# Adafruit_USB_Type_C_Downstream_Breakout_.net
KiCad netlist of a schematic drawn in EAGLE
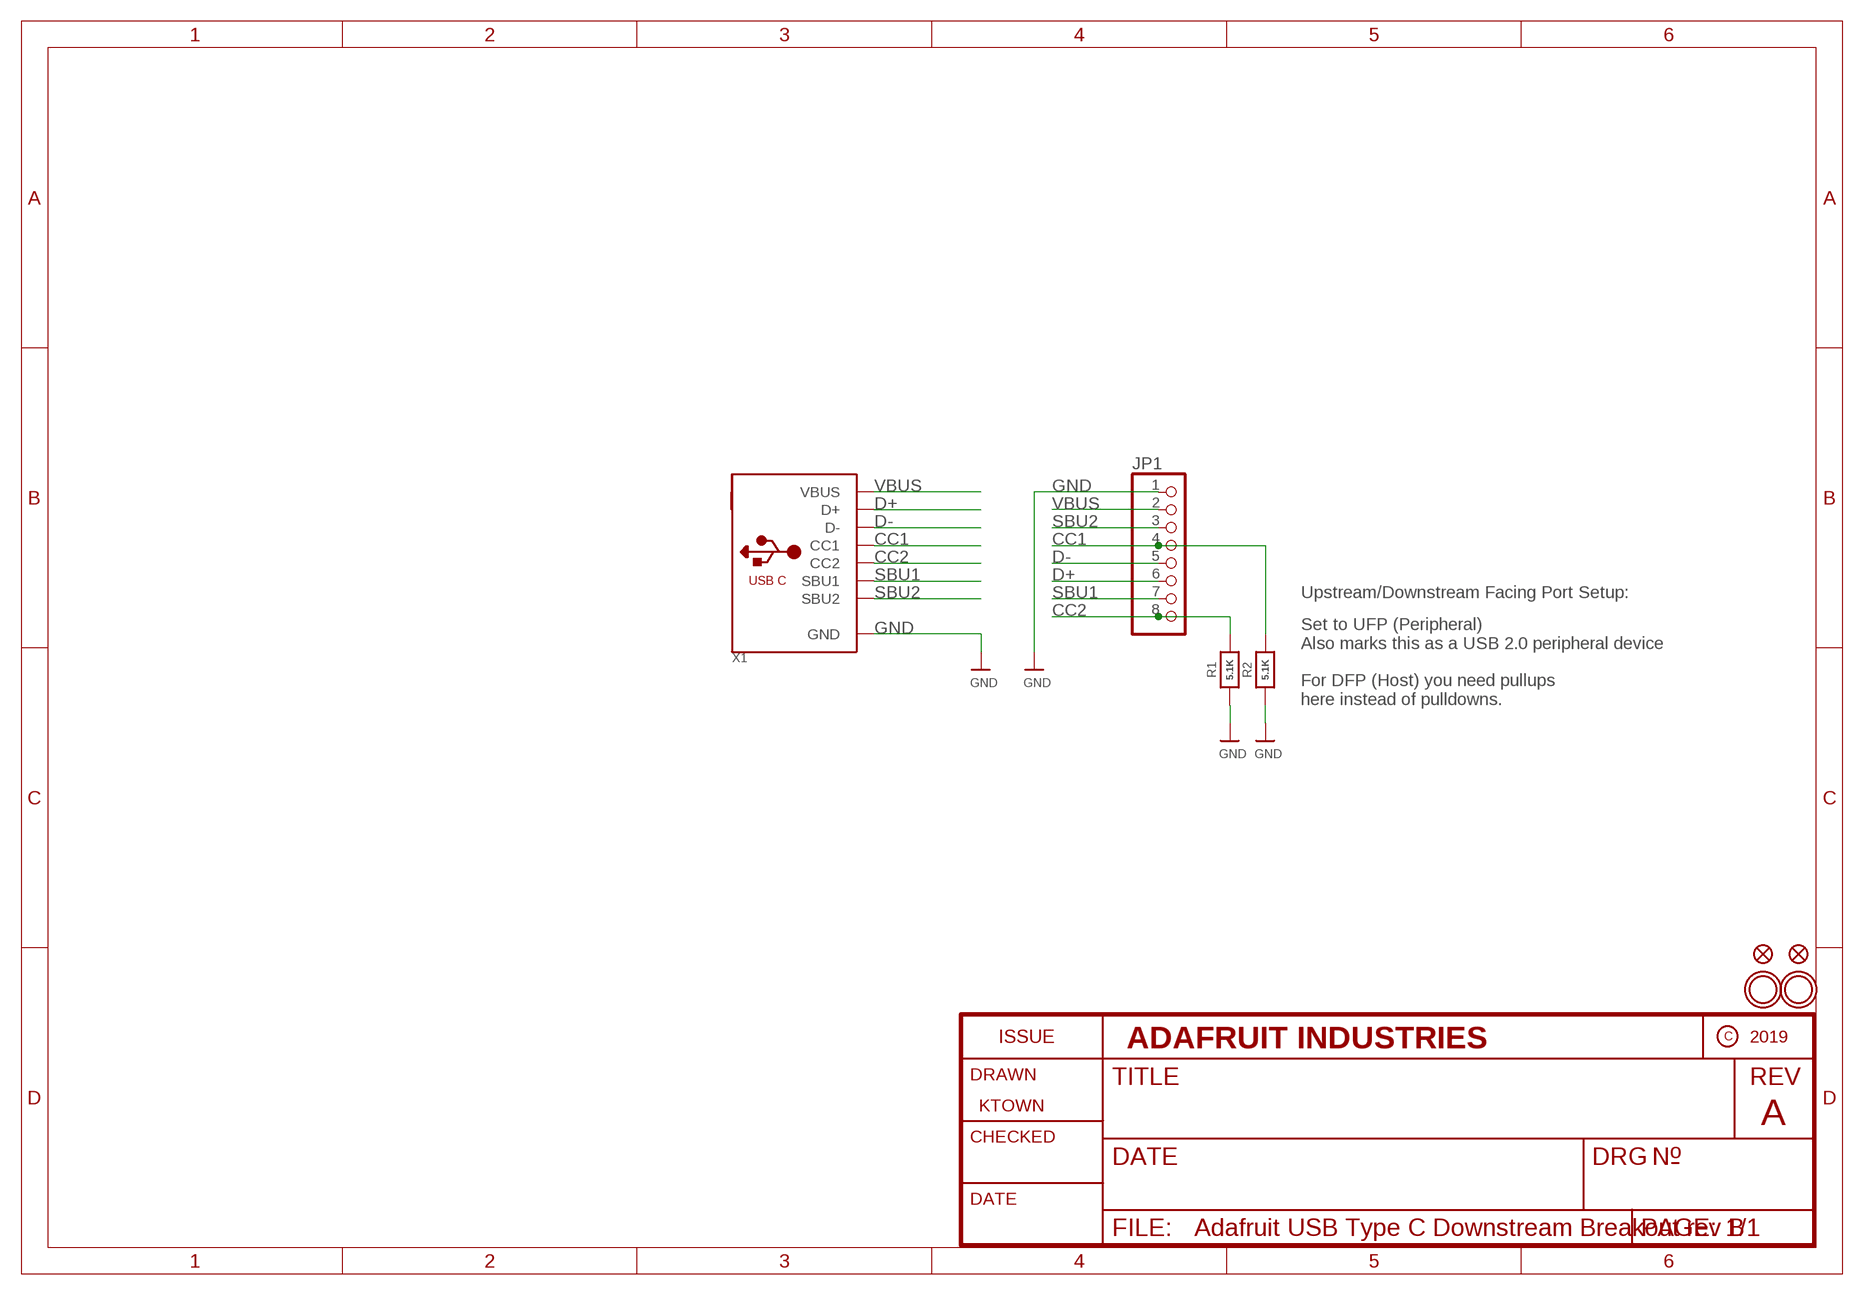
[diagram p0: schematic, sheet 1]

(export (version "E")
  (design (tool "Eeschema 10.0.6"))
  (components
    (comp (ref "FID1")
      (value "FIDUCIAL_1MM")
      (footprint "eagle-import:FIDUCIAL_1MM")
      (libsource (lib "eagle-import") (part "FIDUCIAL_1MM"))
    )
    (comp (ref "FID2")
      (value "FIDUCIAL_1MM")
      (footprint "eagle-import:FIDUCIAL_1MM")
      (libsource (lib "eagle-import") (part "FIDUCIAL_1MM"))
    )
    (comp (ref "JP1")
      (value "HEADER-1X876MIL")
      (footprint "eagle-import:1X08_ROUND_76")
      (libsource (lib "eagle-import") (part "HEADER-1X876MIL"))
    )
    (comp (ref "R1")
      (value "5.1K")
      (footprint "eagle-import:0603-NO")
      (libsource (lib "eagle-import") (part "RESISTOR_0603_NOOUT"))
    )
    (comp (ref "R2")
      (value "5.1K")
      (footprint "eagle-import:0603-NO")
      (libsource (lib "eagle-import") (part "RESISTOR_0603_NOOUT"))
    )
    (comp (ref "U$1")
      (value "MOUNTINGHOLE2.5")
      (footprint "eagle-import:MOUNTINGHOLE_2.5_PLATED")
      (libsource (lib "eagle-import") (part "MOUNTINGHOLE2.5"))
    )
    (comp (ref "U$2")
      (value "MOUNTINGHOLE2.5")
      (footprint "eagle-import:MOUNTINGHOLE_2.5_PLATED")
      (libsource (lib "eagle-import") (part "MOUNTINGHOLE2.5"))
    )
    (comp (ref "X1")
      (value "USB_C")
      (footprint "eagle-import:USB_C_CUSB31-CFM2AX-01-X")
      (libsource (lib "eagle-import") (part "USB_C"))
    )
  )
  (nets
    (net (code "1") (name "/CC1") (class "Default")
      (node (ref "JP1") (pin "4") (pinfunction "4_4") (pintype "passive"))
      (node (ref "R2") (pin "2") (pinfunction "2_2") (pintype "passive"))
      (node (ref "X1") (pin "A5") (pinfunction "CC1_A5") (pintype "bidirectional"))
    )
    (net (code "2") (name "/CC2") (class "Default")
      (node (ref "JP1") (pin "8") (pinfunction "8_8") (pintype "passive"))
      (node (ref "R1") (pin "2") (pinfunction "2_2") (pintype "passive"))
      (node (ref "X1") (pin "B5") (pinfunction "CC2_B5") (pintype "bidirectional"))
    )
    (net (code "3") (name "/D+") (class "Default")
      (node (ref "JP1") (pin "6") (pinfunction "6_6") (pintype "passive"))
      (node (ref "X1") (pin "A6") (pinfunction "D+_A6") (pintype "bidirectional"))
      (node (ref "X1") (pin "B6") (pinfunction "D+_B6") (pintype "bidirectional"))
    )
    (net (code "4") (name "/D-") (class "Default")
      (node (ref "JP1") (pin "5") (pinfunction "5_5") (pintype "passive"))
      (node (ref "X1") (pin "A7") (pinfunction "D-_A7") (pintype "bidirectional"))
      (node (ref "X1") (pin "B7") (pinfunction "D-_B7") (pintype "bidirectional"))
    )
    (net (code "5") (name "/SBU1") (class "Default")
      (node (ref "JP1") (pin "7") (pinfunction "7_7") (pintype "passive"))
      (node (ref "X1") (pin "A8") (pinfunction "SBU1_A8") (pintype "bidirectional"))
    )
    (net (code "6") (name "/SBU2") (class "Default")
      (node (ref "JP1") (pin "3") (pinfunction "3_3") (pintype "passive"))
      (node (ref "X1") (pin "B8") (pinfunction "SBU2_B8") (pintype "bidirectional"))
    )
    (net (code "7") (name "/VBUS") (class "Default")
      (node (ref "JP1") (pin "2") (pinfunction "2_2") (pintype "passive"))
      (node (ref "X1") (pin "A4B9") (pinfunction "VBUS_A4B9") (pintype "power_in"))
      (node (ref "X1") (pin "B4A9") (pinfunction "VBUS_B4A9") (pintype "power_in"))
    )
    (net (code "8") (name "GND") (class "Default")
      (node (ref "JP1") (pin "1") (pinfunction "1_1") (pintype "passive"))
      (node (ref "R1") (pin "1") (pinfunction "1_1") (pintype "passive"))
      (node (ref "R2") (pin "1") (pinfunction "1_1") (pintype "passive"))
      (node (ref "X1") (pin "A1B12") (pinfunction "GND_A1B12") (pintype "power_in"))
      (node (ref "X1") (pin "B1A12") (pinfunction "GND_B1A12") (pintype "power_in"))
    )
  )
)
